# POWER.net
KiCad netlist of a schematic drawn in Altium Designer
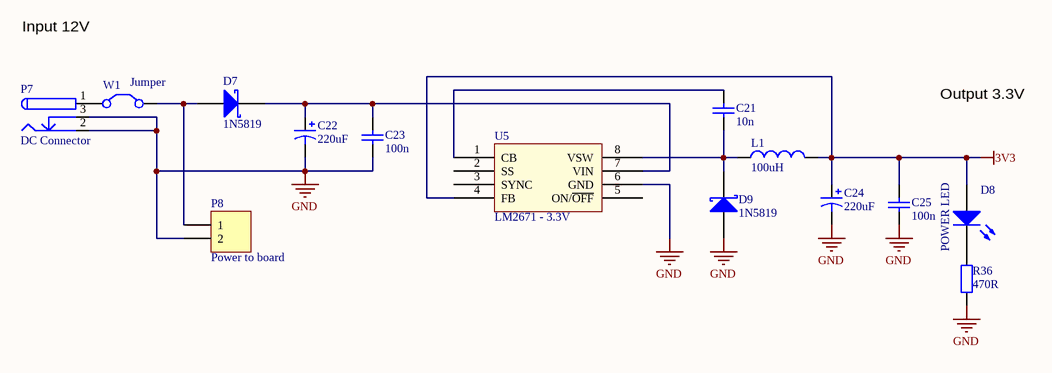
[diagram p0: POWER.SchDoc]

(export (version "E")
  (design (tool "Eeschema 10.0.6"))
  (components
    (comp (ref "C21")
      (value "10n")
      (footprint "1608[0603]")
      (description "Capacitor")
      (fields (field (name "PUBLISHER") "Altium Limited"))
      (libsource (lib "Miscellaneous Devices") (part "Cap"))
    )
    (comp (ref "C22")
      (value "220uF")
      (footprint "SMD CAPACITOR 220uF")
      (description "Capacitor")
      (fields (field (name "PUBLISHER") "Altium Limited"))
      (libsource (lib "Miscellaneous Devices") (part "Cap Pol1"))
    )
    (comp (ref "C23")
      (value "100n")
      (footprint "1608[0603]")
      (description "Capacitor")
      (fields (field (name "PUBLISHER") "Altium Limited"))
      (libsource (lib "Miscellaneous Devices") (part "Cap"))
    )
    (comp (ref "C24")
      (value "220uF")
      (footprint "SMD CAPACITOR 220uF")
      (description "Capacitor")
      (fields (field (name "PUBLISHER") "Altium Limited"))
      (libsource (lib "Miscellaneous Devices") (part "Cap Pol1"))
    )
    (comp (ref "C25")
      (value "100n")
      (footprint "1608[0603]")
      (description "Capacitor")
      (fields (field (name "PUBLISHER") "Altium Limited"))
      (libsource (lib "Miscellaneous Devices") (part "Cap"))
    )
    (comp (ref "D7")
      (value "1N5819")
      (footprint "DO-214AC (SMA)")
      (description "Schottky Diode")
      (fields (field (name "PUBLISHER") "Altium Limited"))
      (libsource (lib "Miscellaneous Devices") (part "D Schottky"))
    )
    (comp (ref "D8")
      (value "POWER LED")
      (footprint "LED-1")
      (description "Typical INFRARED GaAs LED")
      (fields (field (name "PUBLISHER") "Altium Limited"))
      (libsource (lib "Miscellaneous Devices") (part "LED0"))
    )
    (comp (ref "D9")
      (value "1N5819")
      (footprint "DO-214AC (SMA)")
      (description "Schottky Diode")
      (fields (field (name "PUBLISHER") "Altium Limited"))
      (libsource (lib "Miscellaneous Devices") (part "D Schottky"))
    )
    (comp (ref "L1")
      (value "100uH")
      (footprint "SDR0805-101KL")
      (description "Inductor")
      (fields (field (name "PUBLISHER") "Altium Limited"))
      (libsource (lib "Miscellaneous Devices") (part "Inductor"))
    )
    (comp (ref "P7")
      (value "DC Connector")
      (footprint "DC Connector")
      (description "DC Power Connector")
      (libsource (lib "LukaLIBRARY") (part "DC Connector"))
    )
    (comp (ref "P8")
      (value "Power to board")
      (footprint "Block2 - 3.81")
      (description "Header, 2-Pin")
      (fields (field (name "PUBLISHER") "Altium Limited"))
      (libsource (lib "Miscellaneous Connectors") (part "Header 2"))
    )
    (comp (ref "R36")
      (value "470R")
      (footprint "1608[0603]")
      (description "Resistor")
      (fields (field (name "PUBLISHER") "Altium Limited"))
      (libsource (lib "Miscellaneous Devices") (part "Res2"))
    )
    (comp (ref "U5")
      (value "LM2671 - 3.3V")
      (footprint "SOIC8_Narrow")
      (description "Switcher Voltage  Regulator")
      (libsource (lib "LukaLIBRARY") (part "LM2671"))
    )
    (comp (ref "W1")
      (value "Jumper")
      (footprint "HDR1X2")
      (description "Jumper Wire")
      (fields (field (name "PUBLISHER") "Altium Limited"))
      (libsource (lib "Miscellaneous Devices") (part "Jumper"))
    )
  )
  (nets
    (net (code "1") (name "3V3") (class "Default")
      (node (ref "C24") (pin "1") (pinfunction "1_1") (pintype "passive"))
      (node (ref "C25") (pin "1") (pinfunction "1_1") (pintype "passive"))
      (node (ref "D8") (pin "1") (pinfunction "A_1") (pintype "passive"))
      (node (ref "L1") (pin "2") (pinfunction "2_2") (pintype "passive"))
      (node (ref "U5") (pin "4") (pinfunction "FB_4") (pintype "passive"))
    )
    (net (code "2") (name "GND") (class "Default")
      (node (ref "C22") (pin "2") (pinfunction "2_2") (pintype "passive"))
      (node (ref "C23") (pin "2") (pinfunction "2_2") (pintype "passive"))
      (node (ref "C24") (pin "2") (pinfunction "2_2") (pintype "passive"))
      (node (ref "C25") (pin "2") (pinfunction "2_2") (pintype "passive"))
      (node (ref "D9") (pin "1") (pinfunction "A_1") (pintype "passive"))
      (node (ref "P7") (pin "2") (pinfunction "2_2") (pintype "power_in"))
      (node (ref "P7") (pin "3") (pinfunction "3_3") (pintype "power_in"))
      (node (ref "P8") (pin "2") (pinfunction "2_2") (pintype "passive"))
      (node (ref "R36") (pin "1") (pinfunction "1_1") (pintype "passive"))
      (node (ref "U5") (pin "6") (pinfunction "GND_6") (pintype "passive"))
    )
    (net (code "3") (name "Net-(D7-A)") (class "Default")
      (node (ref "D7") (pin "1") (pinfunction "A_1") (pintype "passive"))
      (node (ref "P8") (pin "1") (pinfunction "1_1") (pintype "passive"))
      (node (ref "W1") (pin "2") (pinfunction "C2_2") (pintype "passive"))
    )
    (net (code "4") (name "Net-(D7-K)") (class "Default")
      (node (ref "C22") (pin "1") (pinfunction "1_1") (pintype "passive"))
      (node (ref "C23") (pin "1") (pinfunction "1_1") (pintype "passive"))
      (node (ref "D7") (pin "2") (pinfunction "K_2") (pintype "passive"))
      (node (ref "U5") (pin "7") (pinfunction "VIN_7") (pintype "passive"))
    )
    (net (code "5") (name "Net-(D8-K)") (class "Default")
      (node (ref "D8") (pin "2") (pinfunction "K_2") (pintype "passive"))
      (node (ref "R36") (pin "2") (pinfunction "2_2") (pintype "passive"))
    )
    (net (code "6") (name "Net-(D9-K)") (class "Default")
      (node (ref "C21") (pin "1") (pinfunction "1_1") (pintype "passive"))
      (node (ref "D9") (pin "2") (pinfunction "K_2") (pintype "passive"))
      (node (ref "L1") (pin "1") (pinfunction "1_1") (pintype "passive"))
      (node (ref "U5") (pin "8") (pinfunction "VSW_8") (pintype "passive"))
    )
    (net (code "7") (name "Net-(U5-CB)") (class "Default")
      (node (ref "C21") (pin "2") (pinfunction "2_2") (pintype "passive"))
      (node (ref "U5") (pin "1") (pinfunction "CB_1") (pintype "passive"))
    )
    (net (code "8") (name "Net-(W1-C1)") (class "Default")
      (node (ref "P7") (pin "1") (pinfunction "1_1") (pintype "power_in"))
      (node (ref "W1") (pin "1") (pinfunction "C1_1") (pintype "passive"))
    )
    (net (code "9") (name "unconnected-(U5-ON{slash}~{OFF}-Pad5)") (class "Default")
      (node (ref "U5") (pin "5") (pinfunction "ON/~{OFF}_5") (pintype "passive"))
    )
    (net (code "10") (name "unconnected-(U5-SS-Pad2)") (class "Default")
      (node (ref "U5") (pin "2") (pinfunction "SS_2") (pintype "passive"))
    )
    (net (code "11") (name "unconnected-(U5-SYNC-Pad3)") (class "Default")
      (node (ref "U5") (pin "3") (pinfunction "SYNC_3") (pintype "passive"))
    )
  )
)
